# SmartSensorMainPhase.net
KiCad netlist of a schematic drawn in Altium Designer
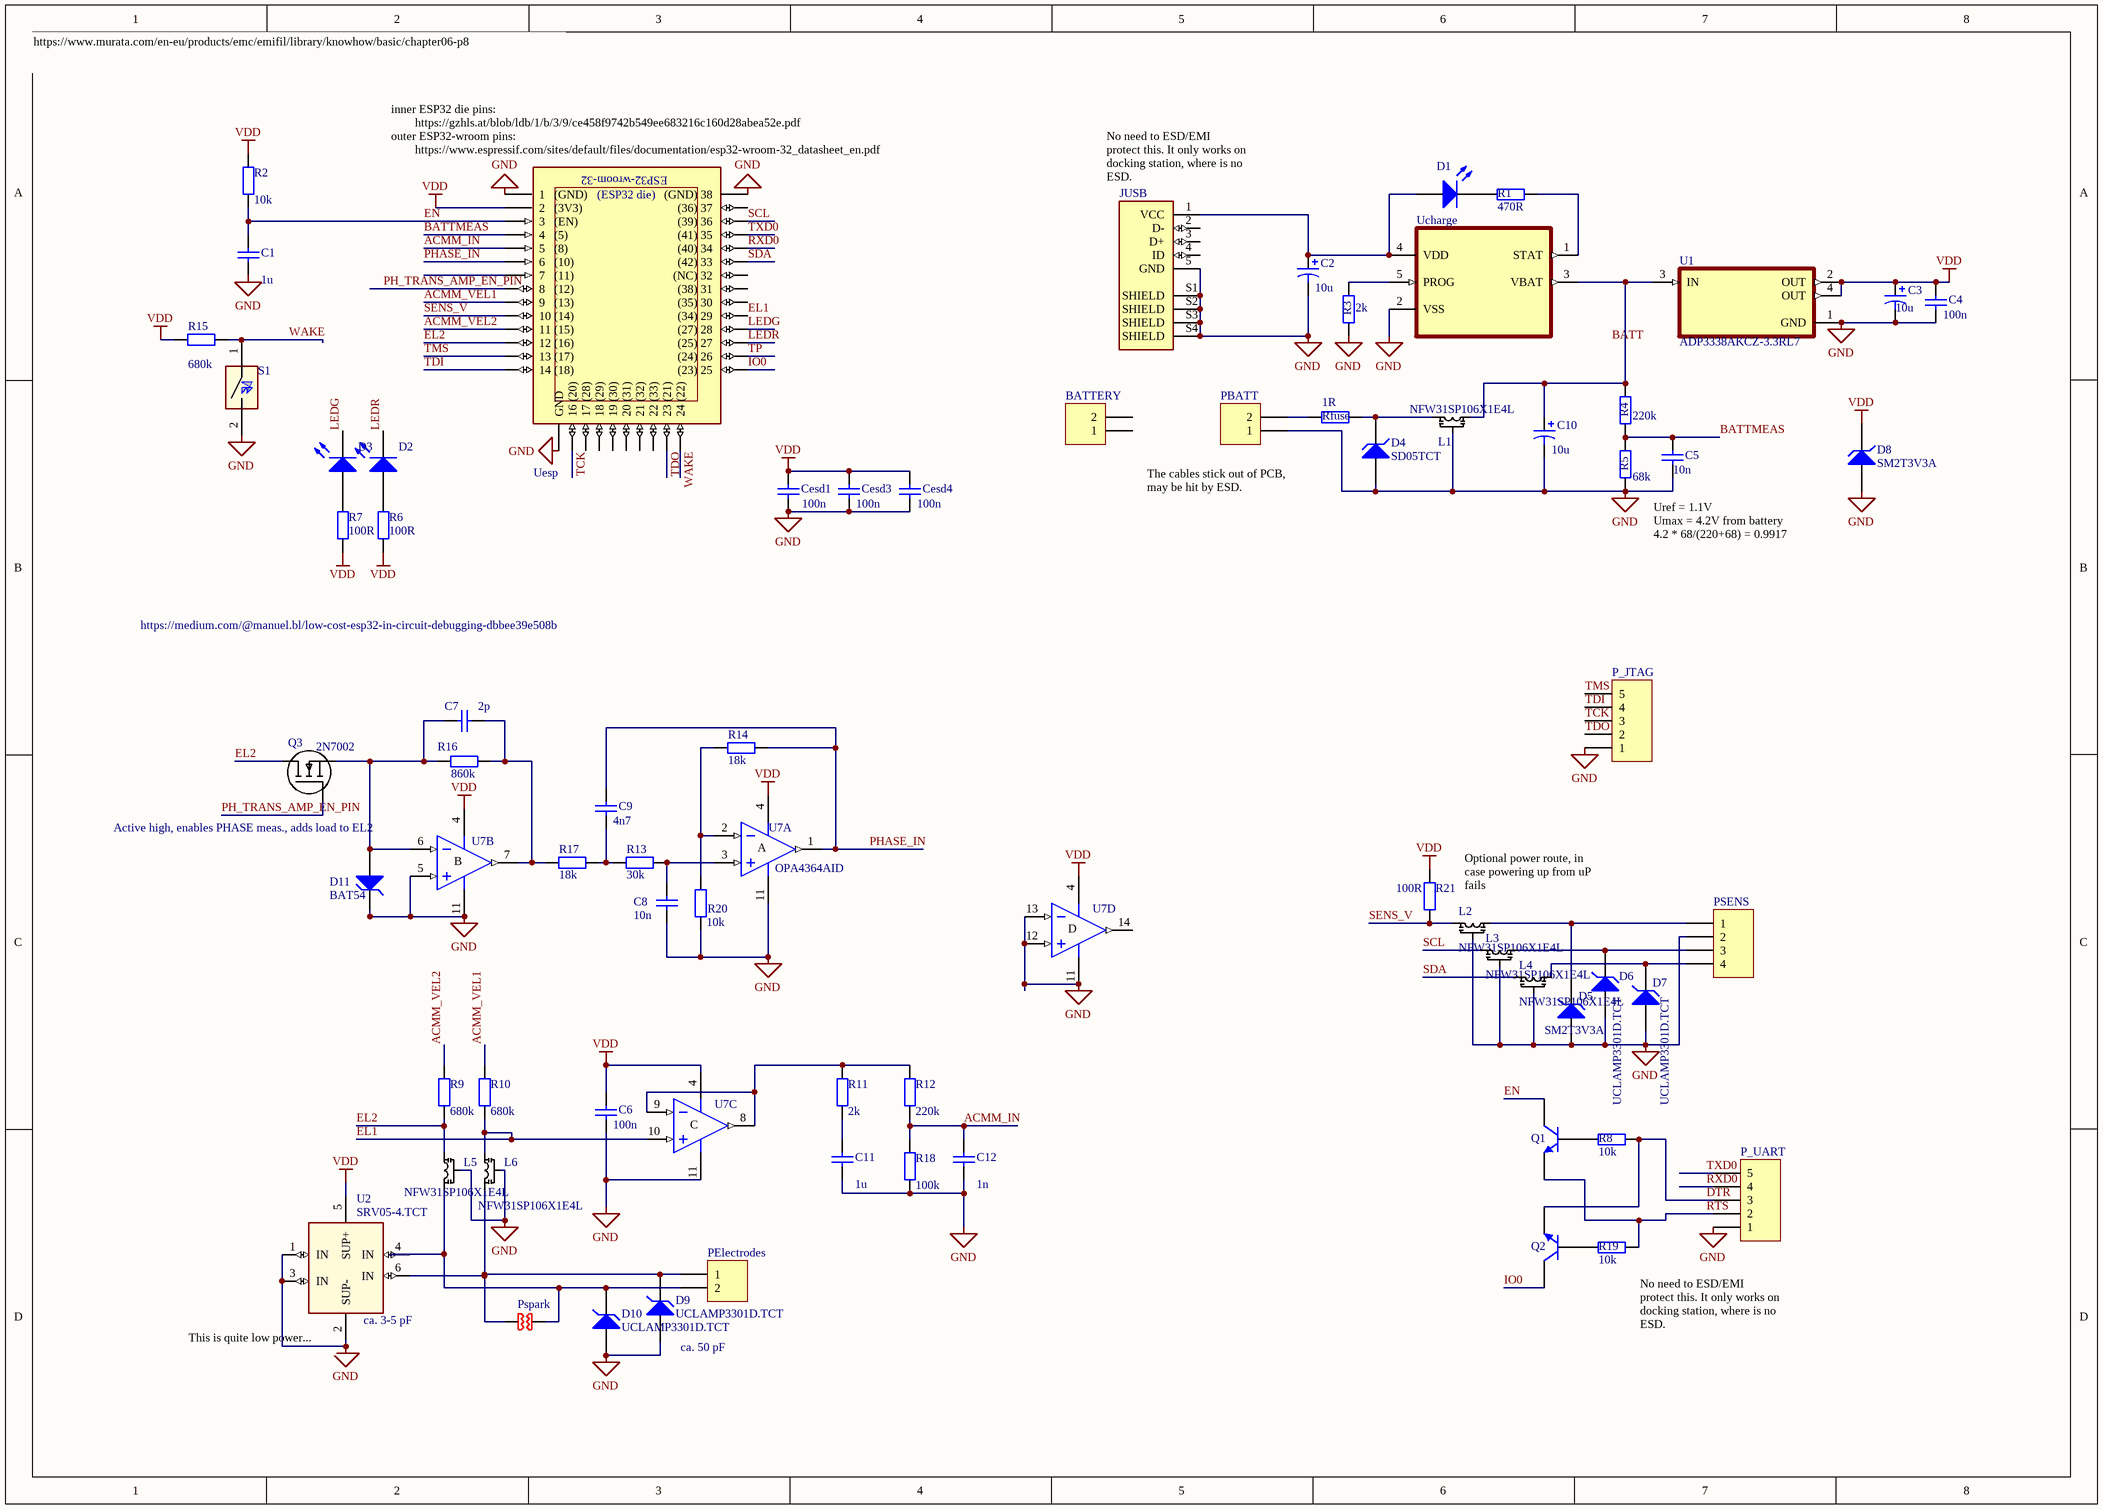
[diagram p0: SmartSensorMainPhase.SchDoc]

(export (version "E")
  (design (tool "Eeschema 10.0.6"))
  (components
    (comp (ref "BATTERY")
      (value "LI-ON 3V7 1200mAh")
      (fields
        (field (name "MP") "UF653450S")
        (field (name "MF") "SANYO")
        (field (name "PUBLISHER") "Altium Limited")
      )
      (libsource (lib "Miscellaneous Connectors") (part "Header 2"))
    )
    (comp (ref "C1")
      (value "1u")
      (footprint "C1206")
      (description "MLCC Capacitor")
      (fields
        (field (name "MF") "any")
        (field (name "MP") "MLCCxxx")
        (field (name "PUBLISHER") "Altium Limited")
      )
      (libsource (lib "Miscellaneous Devices") (part "Cap"))
    )
    (comp (ref "C2")
      (value "10u")
      (footprint "c1206")
      (description "Polarized Capacitor (Surface Mount)")
      (fields (field (name "Comment") "Cap Pol3") (field (name "PUBLISHER") "Altium Limited"))
      (libsource (lib "Miscellaneous Devices") (part "Cap Pol3"))
    )
    (comp (ref "C3")
      (value "10u")
      (footprint "C1206")
      (description "Polarized Capacitor (Surface Mount)")
      (fields (field (name "Comment") "Cap Pol3") (field (name "PUBLISHER") "Altium Limited"))
      (libsource (lib "Miscellaneous Devices") (part "Cap Pol3"))
    )
    (comp (ref "C4")
      (value "100n")
      (footprint "C1206")
      (description "MLCC Capacitor")
      (fields
        (field (name "MF") "any")
        (field (name "MP") "MLCCxxx")
        (field (name "PUBLISHER") "Altium Limited")
      )
      (libsource (lib "Miscellaneous Devices") (part "Cap"))
    )
    (comp (ref "C5")
      (value "10n")
      (footprint "C1206")
      (description "MLCC Capacitor")
      (fields
        (field (name "MF") "any")
        (field (name "MP") "MLCCxxx")
        (field (name "PUBLISHER") "Altium Limited")
      )
      (libsource (lib "Miscellaneous Devices") (part "Cap"))
    )
    (comp (ref "C6")
      (value "100n")
      (footprint "C1206")
      (description "MLCC Capacitor")
      (fields
        (field (name "MF") "any")
        (field (name "MP") "MLCCxxx")
        (field (name "PUBLISHER") "Altium Limited")
      )
      (libsource (lib "Miscellaneous Devices") (part "Cap"))
    )
    (comp (ref "C7")
      (value "2p")
      (footprint "C1206")
      (description "MLCC Capacitor")
      (fields
        (field (name "MF") "any")
        (field (name "MP") "MLCCxxx")
        (field (name "PUBLISHER") "Altium Limited")
      )
      (libsource (lib "Miscellaneous Devices") (part "Cap"))
    )
    (comp (ref "C8")
      (value "10n")
      (footprint "C1206")
      (description "MLCC Capacitor")
      (fields
        (field (name "MF") "any")
        (field (name "MP") "MLCCxxx")
        (field (name "PUBLISHER") "Altium Limited")
      )
      (libsource (lib "Miscellaneous Devices") (part "Cap"))
    )
    (comp (ref "C9")
      (value "4n7")
      (footprint "C1206")
      (description "MLCC Capacitor")
      (fields
        (field (name "MF") "any")
        (field (name "MP") "MLCCxxx")
        (field (name "PUBLISHER") "Altium Limited")
      )
      (libsource (lib "Miscellaneous Devices") (part "Cap"))
    )
    (comp (ref "C10")
      (value "10u")
      (footprint "c1206")
      (description "Polarized Capacitor (Surface Mount)")
      (fields (field (name "Comment") "Cap Pol3") (field (name "PUBLISHER") "Altium Limited"))
      (libsource (lib "Miscellaneous Devices") (part "Cap Pol3"))
    )
    (comp (ref "C11")
      (value "1u")
      (footprint "C1206")
      (description "MLCC Capacitor")
      (fields
        (field (name "MF") "any")
        (field (name "MP") "MLCCxxx")
        (field (name "PUBLISHER") "Altium Limited")
      )
      (libsource (lib "Miscellaneous Devices") (part "Cap"))
    )
    (comp (ref "C12")
      (value "1n")
      (footprint "C1206")
      (description "MLCC Capacitor")
      (fields
        (field (name "MF") "any")
        (field (name "MP") "MLCCxxx")
        (field (name "PUBLISHER") "Altium Limited")
      )
      (libsource (lib "Miscellaneous Devices") (part "Cap"))
    )
    (comp (ref "Cesd1")
      (value "100n")
      (footprint "C1206")
      (description "MLCC Capacitor")
      (fields
        (field (name "MF") "any")
        (field (name "MP") "MLCCxxx")
        (field (name "PUBLISHER") "Altium Limited")
      )
      (libsource (lib "Miscellaneous Devices") (part "Cap"))
    )
    (comp (ref "Cesd3")
      (value "100n")
      (footprint "C1206")
      (description "MLCC Capacitor")
      (fields
        (field (name "MF") "any")
        (field (name "MP") "MLCCxxx")
        (field (name "PUBLISHER") "Altium Limited")
      )
      (libsource (lib "Miscellaneous Devices") (part "Cap"))
    )
    (comp (ref "Cesd4")
      (value "100n")
      (footprint "C1206")
      (description "MLCC Capacitor")
      (fields
        (field (name "MF") "any")
        (field (name "MP") "MLCCxxx")
        (field (name "PUBLISHER") "Altium Limited")
      )
      (libsource (lib "Miscellaneous Devices") (part "Cap"))
    )
    (comp (ref "D1")
      (value "LED RED")
      (footprint "C1206")
      (fields (field (name "PUBLISHER") "Altium Limited"))
      (libsource (lib "Miscellaneous Devices") (part "LED2"))
    )
    (comp (ref "D2")
      (value "LED RED")
      (footprint "C1206")
      (fields (field (name "PUBLISHER") "Altium Limited"))
      (libsource (lib "Miscellaneous Devices") (part "LED2"))
    )
    (comp (ref "D3")
      (value "LED GREEN")
      (footprint "C1206")
      (fields (field (name "PUBLISHER") "Altium Limited"))
      (libsource (lib "Miscellaneous Devices") (part "LED2"))
    )
    (comp (ref "D4")
      (value "SD05TCT")
      (footprint "C1210")
      (description "TVS diode, no latch-up, Vstand-off > 4.5V")
      (fields (field (name "PUBLISHER") "Altium Limited"))
      (libsource (lib "Miscellaneous Devices") (part "D Zener"))
    )
    (comp (ref "D5")
      (value "SM2T3V3A")
      (footprint "C1210")
      (description "TVS Diode, Vstand-off >=3V3, no latch-up")
      (fields (field (name "PUBLISHER") "Altium Limited"))
      (libsource (lib "Miscellaneous Devices") (part "D Zener"))
    )
    (comp (ref "D6")
      (value "UCLAMP3301D.TCT")
      (footprint "C1210")
      (description "TVS diode, Vstand-off >= 3V3, low capacitance, can have latch-up")
      (fields (field (name "PUBLISHER") "Altium Limited"))
      (libsource (lib "Miscellaneous Devices") (part "D Zener"))
    )
    (comp (ref "D7")
      (value "UCLAMP3301D.TCT")
      (footprint "C1210")
      (description "TVS diode, Vstand-off >= 3V3, low capacitance, can have latch-up")
      (fields (field (name "PUBLISHER") "Altium Limited"))
      (libsource (lib "Miscellaneous Devices") (part "D Zener"))
    )
    (comp (ref "D8")
      (value "SM2T3V3A")
      (footprint "C1210")
      (description "TVS Diode, Vstand-off >=3V3, no latch-up")
      (fields (field (name "PUBLISHER") "Altium Limited"))
      (libsource (lib "Miscellaneous Devices") (part "D Zener"))
    )
    (comp (ref "D9")
      (value "UCLAMP3301D.TCT")
      (footprint "C1210")
      (description "TVS diode, Vstand-off >= 3V3, low capacitance, can have latch-up")
      (fields (field (name "PUBLISHER") "Altium Limited"))
      (libsource (lib "Miscellaneous Devices") (part "D Zener"))
    )
    (comp (ref "D10")
      (value "UCLAMP3301D.TCT")
      (footprint "C1210")
      (description "TVS diode, Vstand-off >= 3V3, low capacitance, can have latch-up")
      (fields (field (name "PUBLISHER") "Altium Limited"))
      (libsource (lib "Miscellaneous Devices") (part "D Zener"))
    )
    (comp (ref "D11")
      (value "BAT54")
      (footprint "SOT23_N")
      (description "Zener Diode, super low capacitance")
      (fields (field (name "PUBLISHER") "Altium Limited"))
      (libsource (lib "Miscellaneous Devices") (part "D Zener"))
    )
    (comp (ref "JUSB")
      (value "10118192-0001LF")
      (footprint "GCT_USB3190_REVA2")
      (description "microUSB connector")
      (fields (field (name "MF") "Amphenol"))
      (libsource (lib "USB3190_REVA2") (part "USB3190_REVA2"))
    )
    (comp (ref "L1")
      (value "NFW31SP106X1E4L")
      (footprint "1206 CLC emifil")
      (description "CLCemi")
      (fields (field (name "MF") "Murata") (field (name "PUBLISHER") "Altium Limited"))
      (libsource (lib "SmartSensorLib") (part "CLCemi"))
    )
    (comp (ref "L2")
      (value "NFW31SP106X1E4L")
      (footprint "1206 CLC emifil")
      (description "CLCemi")
      (fields (field (name "MF") "Murata") (field (name "PUBLISHER") "Altium Limited"))
      (libsource (lib "SmartSensorLib") (part "CLCemi"))
    )
    (comp (ref "L3")
      (value "NFW31SP106X1E4L")
      (footprint "1206 CLC emifil")
      (description "CLCemi")
      (fields (field (name "MF") "Murata") (field (name "PUBLISHER") "Altium Limited"))
      (libsource (lib "SmartSensorLib") (part "CLCemi"))
    )
    (comp (ref "L4")
      (value "NFW31SP106X1E4L")
      (footprint "1206 CLC emifil")
      (description "CLCemi")
      (fields (field (name "MF") "Murata") (field (name "PUBLISHER") "Altium Limited"))
      (libsource (lib "SmartSensorLib") (part "CLCemi"))
    )
    (comp (ref "L5")
      (value "NFW31SP106X1E4L")
      (footprint "1206 CLC emifil")
      (description "CLCemi")
      (fields (field (name "MF") "Murata") (field (name "PUBLISHER") "Altium Limited"))
      (libsource (lib "SmartSensorLib") (part "CLCemi"))
    )
    (comp (ref "L6")
      (value "NFW31SP106X1E4L")
      (footprint "1206 CLC emifil")
      (description "CLCemi")
      (fields (field (name "MF") "Murata") (field (name "PUBLISHER") "Altium Limited"))
      (libsource (lib "SmartSensorLib") (part "CLCemi"))
    )
    (comp (ref "PBATT")
      (value "Header 2")
      (footprint "HDR1X2")
      (description "Header, 2-Pin")
      (fields (field (name "PUBLISHER") "Altium Limited"))
      (libsource (lib "Miscellaneous Connectors") (part "Header 2"))
    )
    (comp (ref "PElectrodes")
      (value "Header 2")
      (footprint "HDR1X2")
      (description "Header, 2-Pin")
      (fields (field (name "PUBLISHER") "Altium Limited"))
      (libsource (lib "") (part "Header 2_1"))
    )
    (comp (ref "PSENS")
      (value "Header 4")
      (footprint "HDR1X4")
      (description "Header, 4-Pin")
      (fields (field (name "PUBLISHER") "Altium Limited"))
      (libsource (lib "Miscellaneous Connectors") (part "Header 4"))
    )
    (comp (ref "Pspark")
      (value "spark gap")
      (footprint "SPARKGAP10")
      (libsource (lib "PCB_Project1") (part "SparkGap"))
    )
    (comp (ref "P_JTAG")
      (value "Header 5")
      (footprint "HDR1X5")
      (description "Header, 5-Pin")
      (fields (field (name "PUBLISHER") "Altium Limited"))
      (libsource (lib "Miscellaneous Connectors") (part "Header 5"))
    )
    (comp (ref "P_UART")
      (value "Header 5")
      (footprint "HDR1X5")
      (description "Header, 5-Pin")
      (fields (field (name "PUBLISHER") "Altium Limited"))
      (libsource (lib "Miscellaneous Connectors") (part "Header 5"))
    )
    (comp (ref "Q1")
      (value "NPN")
      (footprint "SOT-23B_N")
      (description "NPN Bipolar Transistor")
      (fields
        (field (name "MP") "SS8050-L")
        (field (name "MF") "YANGJIE TECHNOLOGY")
        (field (name "PUBLISHER") "Altium Limited")
      )
      (libsource (lib "Miscellaneous Devices") (part "QNPN"))
    )
    (comp (ref "Q2")
      (value "NPN")
      (footprint "SOT-23B_N")
      (description "NPN Bipolar Transistor")
      (fields
        (field (name "MP") "SS8050-L")
        (field (name "MF") "YANGJIE TECHNOLOGY")
        (field (name "PUBLISHER") "Altium Limited")
      )
      (libsource (lib "Miscellaneous Devices") (part "QNPN"))
    )
    (comp (ref "Q3")
      (value "2N7002")
      (footprint "SOT23-GDS")
      (description "MOSFET N-CH 60V 115MA SOT-23")
      (fields (field (name "MANUFACTURER") "Fairchild Semiconductor"))
      (libsource (lib "vh_altium_library") (part "2N7002-SOT23"))
    )
    (comp (ref "R1")
      (value "470R")
      (footprint "C1206")
      (description "Resistor 5%")
      (fields (field (name "Comment") "Res2") (field (name "PUBLISHER") "Altium Limited"))
      (libsource (lib "Miscellaneous Devices") (part "Res2"))
    )
    (comp (ref "R2")
      (value "10k")
      (footprint "C1206")
      (description "Resistor 5%")
      (fields (field (name "Comment") "Res2") (field (name "PUBLISHER") "Altium Limited"))
      (libsource (lib "") (part "Res2_2"))
    )
    (comp (ref "R3")
      (value "2k")
      (footprint "C1206")
      (description "Resistor 5%")
      (fields (field (name "Comment") "Res2") (field (name "PUBLISHER") "Altium Limited"))
      (libsource (lib "") (part "Res2_2"))
    )
    (comp (ref "R4")
      (value "220k")
      (footprint "C1206")
      (description "Resistor 1%")
      (fields (field (name "Comment") "Res2") (field (name "PUBLISHER") "Altium Limited"))
      (libsource (lib "") (part "Res2_3"))
    )
    (comp (ref "R5")
      (value "68k")
      (footprint "C1206")
      (description "Resistor 1%")
      (fields (field (name "Comment") "Res2") (field (name "PUBLISHER") "Altium Limited"))
      (libsource (lib "") (part "Res2_3"))
    )
    (comp (ref "R6")
      (value "100R")
      (footprint "C1206")
      (description "Resistor 5%")
      (fields (field (name "Comment") "Res2") (field (name "PUBLISHER") "Altium Limited"))
      (libsource (lib "") (part "Res2_2"))
    )
    (comp (ref "R7")
      (value "100R")
      (footprint "C1206")
      (description "Resistor 5%")
      (fields (field (name "Comment") "Res2") (field (name "PUBLISHER") "Altium Limited"))
      (libsource (lib "") (part "Res2_2"))
    )
    (comp (ref "R8")
      (value "10k")
      (footprint "C1206")
      (description "Resistor 5%")
      (fields (field (name "Comment") "Res2") (field (name "PUBLISHER") "Altium Limited"))
      (libsource (lib "") (part "Res2_2"))
    )
    (comp (ref "R9")
      (value "680k")
      (footprint "C1206")
      (description "Resistor 5%")
      (fields (field (name "Comment") "Res2") (field (name "PUBLISHER") "Altium Limited"))
      (libsource (lib "") (part "Res2_2"))
    )
    (comp (ref "R10")
      (value "680k")
      (footprint "C1206")
      (description "Resistor 5%")
      (fields (field (name "Comment") "Res2") (field (name "PUBLISHER") "Altium Limited"))
      (libsource (lib "") (part "Res2_2"))
    )
    (comp (ref "R11")
      (value "2k")
      (footprint "C1206")
      (description "Resistor 5%")
      (fields (field (name "Comment") "Res2") (field (name "PUBLISHER") "Altium Limited"))
      (libsource (lib "") (part "Res2_2"))
    )
    (comp (ref "R12")
      (value "220k")
      (footprint "C1206")
      (description "Resistor 5%")
      (fields (field (name "Comment") "Res2") (field (name "PUBLISHER") "Altium Limited"))
      (libsource (lib "") (part "Res2_2"))
    )
    (comp (ref "R13")
      (value "30k")
      (footprint "C1206")
      (description "Resistor 1%")
      (fields (field (name "Comment") "Res2") (field (name "PUBLISHER") "Altium Limited"))
      (libsource (lib "Miscellaneous Devices") (part "Res2"))
    )
    (comp (ref "R14")
      (value "18k")
      (footprint "C1206")
      (description "Resistor 1%")
      (fields (field (name "Comment") "Res2") (field (name "PUBLISHER") "Altium Limited"))
      (libsource (lib "Miscellaneous Devices") (part "Res2"))
    )
    (comp (ref "R15")
      (value "680k")
      (footprint "C1206")
      (description "Resistor 5%")
      (fields (field (name "Comment") "Res2") (field (name "PUBLISHER") "Altium Limited"))
      (libsource (lib "Miscellaneous Devices") (part "Res2"))
    )
    (comp (ref "R16")
      (value "860k")
      (footprint "C1206")
      (description "Resistor 1%")
      (fields (field (name "Comment") "Res2") (field (name "PUBLISHER") "Altium Limited"))
      (libsource (lib "Miscellaneous Devices") (part "Res2"))
    )
    (comp (ref "R17")
      (value "18k")
      (footprint "C1206")
      (description "Resistor 1%")
      (fields (field (name "Comment") "Res2") (field (name "PUBLISHER") "Altium Limited"))
      (libsource (lib "Miscellaneous Devices") (part "Res2"))
    )
    (comp (ref "R18")
      (value "100k")
      (footprint "C1206")
      (description "Resistor 5%")
      (fields (field (name "Comment") "Res2") (field (name "PUBLISHER") "Altium Limited"))
      (libsource (lib "") (part "Res2_2"))
    )
    (comp (ref "R19")
      (value "10k")
      (footprint "C1206")
      (description "Resistor 5%")
      (fields (field (name "Comment") "Res2") (field (name "PUBLISHER") "Altium Limited"))
      (libsource (lib "") (part "Res2_2"))
    )
    (comp (ref "R20")
      (value "10k")
      (footprint "C1206")
      (description "Resistor 1%")
      (fields (field (name "Comment") "Res2") (field (name "PUBLISHER") "Altium Limited"))
      (libsource (lib "") (part "Res2_1"))
    )
    (comp (ref "R21")
      (value "100R")
      (footprint "c1206")
      (description "Resistor 5%")
      (fields (field (name "Comment") "Res2") (field (name "PUBLISHER") "Altium Limited"))
      (libsource (lib "") (part "Res2_2"))
    )
    (comp (ref "Rfuse")
      (value "1R")
      (footprint "C1206")
      (description "Resistor 5%")
      (fields (field (name "Comment") "Res2") (field (name "PUBLISHER") "Altium Limited"))
      (libsource (lib "") (part "Res2_1"))
    )
    (comp (ref "S1")
      (value "VBS030600")
      (footprint "VBS030600")
      (description "Movement sensor")
      (fields (field (name "MF") "ONCQUE"))
      (libsource (lib "SRV05-4.TCT") (part "VBS030600"))
    )
    (comp (ref "U1")
      (value "ADP3338AKCZ-3.3RL7")
      (footprint "SOT230P700X180-4N")
      (description "LDO voltage regulator")
      (fields (field (name "MF") "Analog Devices"))
      (libsource (lib "ADP3338AKCZ-5-R7") (part "ADP3338AKCZ-5-R7"))
    )
    (comp (ref "U2")
      (value "SRV05-4.TCT")
      (footprint "SRV05-4.TCT:SOT95P280X145-6N")
      (description "17.5V Clamp 12A _8/20µs_ Ipp Tvs Diode Surface Mount SOT-23-6")
      (fields (field (name "MF") "Semtech"))
      (libsource (lib "SnapEDAsch") (part "SRV05-4.TCT"))
    )
    (comp (ref "U7")
      (value "OPA4364AID")
      (footprint "SO-14_N")
      (description "Quad Picoampere Input Current Bipolar Operational Amplifier")
      (fields (field (name "MF") "TI") (field (name "PUBLISHER") "Altium Limited"))
      (libsource (lib "AD Operational Amplifier") (part "AD704AN"))
    )
    (comp (ref "Ucharge")
      (value "MCP73831T-2ACI/OT")
      (footprint "SOT23-5")
      (description "Charger IC Lithium Ion/Polymer SOT-23-5")
      (fields (field (name "MF") "Microchip"))
      (libsource (lib "MCP73831T-2ACI_OT") (part "MCP73831T-2ACI/OT"))
    )
    (comp (ref "Uesp")
      (value "ESP32-WROOM-32")
      (footprint "ESP32-WROOM-32:MODULE_ESP32-WROOM-32")
      (description "Bluetooth, WiFi Transceiver Module 2.4GHz ~ 2.5GHz Surface Mount")
      (fields (field (name "MF") "Espressif Systems") (field (name "DIGI-KEY_PART_NUMBER") "1904-1010-1-ND"))
      (libsource (lib "PCB_Project1") (part "ESP32-WROOM-32"))
    )
  )
  (nets
    (net (code "1") (name "/ACMM_IN") (class "Default")
      (node (ref "C12") (pin "2") (pinfunction "2_2") (pintype "passive"))
      (node (ref "R12") (pin "1") (pinfunction "1_1") (pintype "passive"))
      (node (ref "R18") (pin "2") (pinfunction "2_2") (pintype "passive"))
      (node (ref "Uesp") (pin "5") (pinfunction "5___(8)_5") (pintype "input"))
    )
    (net (code "2") (name "/ACMM_VEL1") (class "Default")
      (node (ref "R10") (pin "2") (pinfunction "2_2") (pintype "passive"))
      (node (ref "Uesp") (pin "9") (pinfunction "9___(13)_9") (pintype "bidirectional"))
    )
    (net (code "3") (name "/ACMM_VEL2") (class "Default")
      (node (ref "R9") (pin "2") (pinfunction "2_2") (pintype "passive"))
      (node (ref "Uesp") (pin "11") (pinfunction "11_(15)_11") (pintype "bidirectional"))
    )
    (net (code "5") (name "/BATTMEAS") (class "Default")
      (node (ref "C5") (pin "2") (pinfunction "2_2") (pintype "passive"))
      (node (ref "R4") (pin "1") (pinfunction "1_1") (pintype "passive"))
      (node (ref "R5") (pin "2") (pinfunction "2_2") (pintype "passive"))
      (node (ref "Uesp") (pin "4") (pinfunction "4___(5)_4") (pintype "input"))
    )
    (net (code "6") (name "/DTR") (class "Default")
      (node (ref "P_UART") (pin "3") (pinfunction "3_3") (pintype "passive"))
      (node (ref "Q2") (pin "2") (pinfunction "E_2") (pintype "passive"))
      (node (ref "R8") (pin "2") (pinfunction "2_2") (pintype "passive"))
    )
    (net (code "7") (name "/EL1") (class "Default")
      (node (ref "L6") (pin "3") (pinfunction "3_3") (pintype "passive"))
      (node (ref "R10") (pin "1") (pinfunction "1_1") (pintype "passive"))
      (node (ref "U7") (pin "10") (pinfunction "IN+_10") (pintype "input"))
      (node (ref "Uesp") (pin "29") (pinfunction "(34)_29_29") (pintype "bidirectional"))
    )
    (net (code "8") (name "/EL2") (class "Default")
      (node (ref "L5") (pin "3") (pinfunction "3_3") (pintype "passive"))
      (node (ref "Q3") (pin "D") (pintype "passive"))
      (node (ref "R9") (pin "1") (pinfunction "1_1") (pintype "passive"))
      (node (ref "Uesp") (pin "12") (pinfunction "12_(16)_12") (pintype "bidirectional"))
    )
    (net (code "9") (name "/EN") (class "Default")
      (node (ref "C1") (pin "2") (pinfunction "2_2") (pintype "passive"))
      (node (ref "Q1") (pin "3") (pinfunction "C_3") (pintype "passive"))
      (node (ref "R2") (pin "1") (pinfunction "1_1") (pintype "passive"))
      (node (ref "Uesp") (pin "3") (pinfunction "3___(EN)_3") (pintype "input"))
    )
    (net (code "10") (name "/IO0") (class "Default")
      (node (ref "Q2") (pin "3") (pinfunction "C_3") (pintype "passive"))
      (node (ref "Uesp") (pin "25") (pinfunction "(23)_25_25") (pintype "bidirectional"))
    )
    (net (code "11") (name "/LEDG") (class "Default")
      (node (ref "D3") (pin "2") (pinfunction "K_2") (pintype "passive"))
      (node (ref "Uesp") (pin "28") (pinfunction "(27)_28_28") (pintype "bidirectional"))
    )
    (net (code "12") (name "/LEDR") (class "Default")
      (node (ref "D2") (pin "2") (pinfunction "K_2") (pintype "passive"))
      (node (ref "Uesp") (pin "27") (pinfunction "(25)_27_27") (pintype "bidirectional"))
    )
    (net (code "13") (name "/PHASE_IN") (class "Default")
      (node (ref "C9") (pin "2") (pinfunction "2_2") (pintype "passive"))
      (node (ref "R14") (pin "1") (pinfunction "1_1") (pintype "passive"))
      (node (ref "U7") (pin "1") (pinfunction "OUT_1") (pintype "output"))
      (node (ref "Uesp") (pin "6") (pinfunction "6___(10)_6") (pintype "input"))
    )
    (net (code "14") (name "/PH_TRANS_AMP_EN_PIN") (class "Default")
      (node (ref "Q3") (pin "G") (pintype "passive"))
      (node (ref "Uesp") (pin "8") (pinfunction "8___(12)_8") (pintype "bidirectional"))
    )
    (net (code "15") (name "/RTS") (class "Default")
      (node (ref "P_UART") (pin "2") (pinfunction "2_2") (pintype "passive"))
      (node (ref "Q1") (pin "2") (pinfunction "E_2") (pintype "passive"))
      (node (ref "R19") (pin "2") (pinfunction "2_2") (pintype "passive"))
    )
    (net (code "16") (name "/RXD0") (class "Default")
      (node (ref "P_UART") (pin "4") (pinfunction "4_4") (pintype "passive"))
      (node (ref "Uesp") (pin "34") (pinfunction "(40)_34_34") (pintype "bidirectional"))
    )
    (net (code "17") (name "/SCL") (class "Default")
      (node (ref "L3") (pin "1") (pinfunction "1_1") (pintype "passive"))
      (node (ref "Uesp") (pin "36") (pinfunction "(39)_36_36") (pintype "bidirectional"))
    )
    (net (code "18") (name "/SDA") (class "Default")
      (node (ref "L4") (pin "1") (pinfunction "1_1") (pintype "passive"))
      (node (ref "Uesp") (pin "33") (pinfunction "(42)_33_33") (pintype "bidirectional"))
    )
    (net (code "19") (name "/SENS_V") (class "Default")
      (node (ref "L2") (pin "1") (pinfunction "1_1") (pintype "passive"))
      (node (ref "R21") (pin "1") (pinfunction "1_1") (pintype "passive"))
      (node (ref "Uesp") (pin "10") (pinfunction "10_(14)_10") (pintype "bidirectional"))
    )
    (net (code "20") (name "/TCK") (class "Default")
      (node (ref "P_JTAG") (pin "3") (pinfunction "3_3") (pintype "passive"))
      (node (ref "Uesp") (pin "16") (pinfunction "16_(20)_16") (pintype "bidirectional"))
    )
    (net (code "21") (name "/TDI") (class "Default")
      (node (ref "P_JTAG") (pin "4") (pinfunction "4_4") (pintype "passive"))
      (node (ref "Uesp") (pin "14") (pinfunction "14_(18)_14") (pintype "bidirectional"))
    )
    (net (code "22") (name "/TDO") (class "Default")
      (node (ref "P_JTAG") (pin "2") (pinfunction "2_2") (pintype "passive"))
      (node (ref "Uesp") (pin "23") (pinfunction "23_(21)_23") (pintype "bidirectional"))
    )
    (net (code "23") (name "/TMS") (class "Default")
      (node (ref "P_JTAG") (pin "5") (pinfunction "5_5") (pintype "passive"))
      (node (ref "Uesp") (pin "13") (pinfunction "13_(17)_13") (pintype "bidirectional"))
    )
    (net (code "24") (name "/TP") (class "Default")
      (node (ref "Uesp") (pin "26") (pinfunction "(24)_26_26") (pintype "bidirectional"))
    )
    (net (code "25") (name "/TXD0") (class "Default")
      (node (ref "P_UART") (pin "5") (pinfunction "5_5") (pintype "passive"))
      (node (ref "Uesp") (pin "35") (pinfunction "(41)_35_35") (pintype "bidirectional"))
    )
    (net (code "26") (name "/WAKE") (class "Default")
      (node (ref "R15") (pin "1") (pinfunction "1_1") (pintype "passive"))
      (node (ref "S1") (pin "1") (pinfunction "IN_1") (pintype "open_collector"))
      (node (ref "Uesp") (pin "24") (pinfunction "24_(22)_24") (pintype "bidirectional"))
    )
    (net (code "27") (name "GND") (class "Default")
      (node (ref "C1") (pin "1") (pinfunction "1_1") (pintype "passive"))
      (node (ref "C10") (pin "2") (pinfunction "2_2") (pintype "passive"))
      (node (ref "C11") (pin "1") (pinfunction "1_1") (pintype "passive"))
      (node (ref "C12") (pin "1") (pinfunction "1_1") (pintype "passive"))
      (node (ref "C2") (pin "2") (pinfunction "2_2") (pintype "passive"))
      (node (ref "C3") (pin "2") (pinfunction "2_2") (pintype "passive"))
      (node (ref "C4") (pin "1") (pinfunction "1_1") (pintype "passive"))
      (node (ref "C5") (pin "1") (pinfunction "1_1") (pintype "passive"))
      (node (ref "C6") (pin "1") (pinfunction "1_1") (pintype "passive"))
      (node (ref "C8") (pin "1") (pinfunction "1_1") (pintype "passive"))
      (node (ref "Cesd1") (pin "1") (pinfunction "1_1") (pintype "passive"))
      (node (ref "Cesd3") (pin "1") (pinfunction "1_1") (pintype "passive"))
      (node (ref "Cesd4") (pin "1") (pinfunction "1_1") (pintype "passive"))
      (node (ref "D10") (pin "1") (pinfunction "A_1") (pintype "passive"))
      (node (ref "D11") (pin "2") (pinfunction "K_2") (pintype "passive"))
      (node (ref "D4") (pin "1") (pinfunction "A_1") (pintype "passive"))
      (node (ref "D5") (pin "1") (pinfunction "A_1") (pintype "passive"))
      (node (ref "D6") (pin "1") (pinfunction "A_1") (pintype "passive"))
      (node (ref "D7") (pin "1") (pinfunction "A_1") (pintype "passive"))
      (node (ref "D8") (pin "1") (pinfunction "A_1") (pintype "passive"))
      (node (ref "D9") (pin "1") (pinfunction "A_1") (pintype "passive"))
      (node (ref "JUSB") (pin "5") (pinfunction "GND_5") (pintype "power_in"))
      (node (ref "JUSB") (pin "S1") (pinfunction "SHIELD_S1") (pintype "passive"))
      (node (ref "JUSB") (pin "S2") (pinfunction "SHIELD_S2") (pintype "passive"))
      (node (ref "JUSB") (pin "S3") (pinfunction "SHIELD_S3") (pintype "passive"))
      (node (ref "JUSB") (pin "S4") (pinfunction "SHIELD_S4") (pintype "passive"))
      (node (ref "L1") (pin "2") (pinfunction "2_2") (pintype "power_in"))
      (node (ref "L2") (pin "2") (pinfunction "2_2") (pintype "power_in"))
      (node (ref "L3") (pin "2") (pinfunction "2_2") (pintype "power_in"))
      (node (ref "L4") (pin "2") (pinfunction "2_2") (pintype "power_in"))
      (node (ref "L5") (pin "2") (pinfunction "2_2") (pintype "power_in"))
      (node (ref "L6") (pin "2") (pinfunction "2_2") (pintype "power_in"))
      (node (ref "PBATT") (pin "1") (pinfunction "1_1") (pintype "passive"))
      (node (ref "PSENS") (pin "2") (pinfunction "2_2") (pintype "passive"))
      (node (ref "P_JTAG") (pin "1") (pinfunction "1_1") (pintype "passive"))
      (node (ref "P_UART") (pin "1") (pinfunction "1_1") (pintype "passive"))
      (node (ref "R18") (pin "1") (pinfunction "1_1") (pintype "passive"))
      (node (ref "R20") (pin "2") (pinfunction "2_2") (pintype "passive"))
      (node (ref "R3") (pin "1") (pinfunction "1_1") (pintype "passive"))
      (node (ref "R5") (pin "1") (pinfunction "1_1") (pintype "passive"))
      (node (ref "S1") (pin "2") (pinfunction "IN_2") (pintype "open_collector"))
      (node (ref "U1") (pin "1") (pinfunction "GND_1") (pintype "power_in"))
      (node (ref "U2") (pin "1") (pinfunction "IN_1") (pintype "bidirectional"))
      (node (ref "U2") (pin "2") (pinfunction "SUP-_2") (pintype "power_in"))
      (node (ref "U2") (pin "3") (pinfunction "IN_3") (pintype "bidirectional"))
      (node (ref "U7") (pin "11") (pinfunction "V-_11") (pintype "power_in"))
      (node (ref "U7") (pin "12") (pinfunction "IN+_12") (pintype "input"))
      (node (ref "U7") (pin "13") (pinfunction "IN-_13") (pintype "input"))
      (node (ref "U7") (pin "5") (pinfunction "IN+_5") (pintype "input"))
      (node (ref "Ucharge") (pin "2") (pinfunction "VSS_2") (pintype "power_in"))
      (node (ref "Uesp") (pin "1") (pinfunction "1___(GND)_1") (pintype "power_in"))
      (node (ref "Uesp") (pin "15") (pinfunction "GND_15") (pintype "power_in"))
      (node (ref "Uesp") (pin "38") (pinfunction "(GND)_38_38") (pintype "power_in"))
    )
    (net (code "28") (name "Net-(C9-Pad1)") (class "Default")
      (node (ref "C9") (pin "1") (pinfunction "1_1") (pintype "passive"))
      (node (ref "R13") (pin "2") (pinfunction "2_2") (pintype "passive"))
      (node (ref "R17") (pin "1") (pinfunction "1_1") (pintype "passive"))
    )
    (net (code "29") (name "Net-(C11-Pad2)") (class "Default")
      (node (ref "C11") (pin "2") (pinfunction "2_2") (pintype "passive"))
      (node (ref "R11") (pin "1") (pinfunction "1_1") (pintype "passive"))
    )
    (net (code "30") (name "Net-(D1-A)") (class "Default")
      (node (ref "C2") (pin "1") (pinfunction "1_1") (pintype "passive"))
      (node (ref "D1") (pin "1") (pinfunction "A_1") (pintype "passive"))
      (node (ref "JUSB") (pin "1") (pinfunction "VCC_1") (pintype "power_in"))
      (node (ref "Ucharge") (pin "4") (pinfunction "VDD_4") (pintype "power_in"))
    )
    (net (code "31") (name "Net-(D1-K)") (class "Default")
      (node (ref "D1") (pin "2") (pinfunction "K_2") (pintype "passive"))
      (node (ref "R1") (pin "2") (pinfunction "2_2") (pintype "passive"))
    )
    (net (code "32") (name "Net-(D2-A)") (class "Default")
      (node (ref "D2") (pin "1") (pinfunction "A_1") (pintype "passive"))
      (node (ref "R6") (pin "2") (pinfunction "2_2") (pintype "passive"))
    )
    (net (code "33") (name "Net-(D3-A)") (class "Default")
      (node (ref "D3") (pin "1") (pinfunction "A_1") (pintype "passive"))
      (node (ref "R7") (pin "2") (pinfunction "2_2") (pintype "passive"))
    )
    (net (code "34") (name "Net-(D4-K)") (class "Default")
      (node (ref "D4") (pin "2") (pinfunction "K_2") (pintype "passive"))
      (node (ref "L1") (pin "1") (pinfunction "1_1") (pintype "passive"))
      (node (ref "Rfuse") (pin "1") (pinfunction "1_1") (pintype "passive"))
    )
    (net (code "35") (name "Net-(D5-K)") (class "Default")
      (node (ref "D5") (pin "2") (pinfunction "K_2") (pintype "passive"))
      (node (ref "L2") (pin "3") (pinfunction "3_3") (pintype "passive"))
      (node (ref "PSENS") (pin "1") (pinfunction "1_1") (pintype "passive"))
    )
    (net (code "36") (name "Net-(D6-K)") (class "Default")
      (node (ref "D6") (pin "2") (pinfunction "K_2") (pintype "passive"))
      (node (ref "L3") (pin "3") (pinfunction "3_3") (pintype "passive"))
      (node (ref "PSENS") (pin "3") (pinfunction "3_3") (pintype "passive"))
    )
    (net (code "37") (name "Net-(D7-K)") (class "Default")
      (node (ref "D7") (pin "2") (pinfunction "K_2") (pintype "passive"))
      (node (ref "L4") (pin "3") (pinfunction "3_3") (pintype "passive"))
      (node (ref "PSENS") (pin "4") (pinfunction "4_4") (pintype "passive"))
    )
    (net (code "38") (name "Net-(D9-K)") (class "Default")
      (node (ref "D9") (pin "2") (pinfunction "K_2") (pintype "passive"))
      (node (ref "L6") (pin "1") (pinfunction "1_1") (pintype "passive"))
      (node (ref "PElectrodes") (pin "1") (pinfunction "1_1") (pintype "passive"))
      (node (ref "Pspark") (pin "1") (pinfunction "1_1") (pintype "passive"))
      (node (ref "U2") (pin "6") (pinfunction "IN_6") (pintype "bidirectional"))
    )
    (net (code "39") (name "Net-(D10-K)") (class "Default")
      (node (ref "D10") (pin "2") (pinfunction "K_2") (pintype "passive"))
      (node (ref "L5") (pin "1") (pinfunction "1_1") (pintype "passive"))
      (node (ref "PElectrodes") (pin "2") (pinfunction "2_2") (pintype "passive"))
      (node (ref "Pspark") (pin "2") (pinfunction "2_2") (pintype "passive"))
      (node (ref "U2") (pin "4") (pinfunction "IN_4") (pintype "bidirectional"))
    )
    (net (code "40") (name "Net-(D11-A)") (class "Default")
      (node (ref "C7") (pin "2") (pinfunction "2_2") (pintype "passive"))
      (node (ref "D11") (pin "1") (pinfunction "A_1") (pintype "passive"))
      (node (ref "Q3") (pin "S") (pintype "passive"))
      (node (ref "R16") (pin "2") (pinfunction "2_2") (pintype "passive"))
      (node (ref "U7") (pin "6") (pinfunction "IN-_6") (pintype "input"))
    )
    (net (code "41") (name "Net-(PBATT-Pad2)") (class "Default")
      (node (ref "PBATT") (pin "2") (pinfunction "2_2") (pintype "passive"))
      (node (ref "Rfuse") (pin "2") (pinfunction "2_2") (pintype "passive"))
    )
    (net (code "42") (name "Net-(Q1-B)") (class "Default")
      (node (ref "Q1") (pin "1") (pinfunction "B_1") (pintype "passive"))
      (node (ref "R8") (pin "1") (pinfunction "1_1") (pintype "passive"))
    )
    (net (code "43") (name "Net-(Q2-B)") (class "Default")
      (node (ref "Q2") (pin "1") (pinfunction "B_1") (pintype "passive"))
      (node (ref "R19") (pin "1") (pinfunction "1_1") (pintype "passive"))
    )
    (net (code "44") (name "Net-(U1-IN)") (class "Default")
      (node (ref "C10") (pin "1") (pinfunction "1_1") (pintype "passive"))
      (node (ref "L1") (pin "3") (pinfunction "3_3") (pintype "passive"))
      (node (ref "R4") (pin "2") (pinfunction "2_2") (pintype "passive"))
      (node (ref "U1") (pin "3") (pinfunction "IN_3") (pintype "input"))
      (node (ref "Ucharge") (pin "3") (pinfunction "VBAT_3") (pintype "output"))
    )
    (net (code "45") (name "Net-(U7A-IN+)") (class "Default")
      (node (ref "C8") (pin "2") (pinfunction "2_2") (pintype "passive"))
      (node (ref "R13") (pin "1") (pinfunction "1_1") (pintype "passive"))
      (node (ref "U7") (pin "3") (pinfunction "IN+_3") (pintype "input"))
    )
    (net (code "46") (name "Net-(U7A-IN-)") (class "Default")
      (node (ref "R14") (pin "2") (pinfunction "2_2") (pintype "passive"))
      (node (ref "R20") (pin "1") (pinfunction "1_1") (pintype "passive"))
      (node (ref "U7") (pin "2") (pinfunction "IN-_2") (pintype "input"))
    )
    (net (code "47") (name "Net-(U7B-OUT)") (class "Default")
      (node (ref "C7") (pin "1") (pinfunction "1_1") (pintype "passive"))
      (node (ref "R16") (pin "1") (pinfunction "1_1") (pintype "passive"))
      (node (ref "R17") (pin "2") (pinfunction "2_2") (pintype "passive"))
      (node (ref "U7") (pin "7") (pinfunction "OUT_7") (pintype "output"))
    )
    (net (code "48") (name "Net-(U7C-IN-)") (class "Default")
      (node (ref "R11") (pin "2") (pinfunction "2_2") (pintype "passive"))
      (node (ref "R12") (pin "2") (pinfunction "2_2") (pintype "passive"))
      (node (ref "U7") (pin "8") (pinfunction "OUT_8") (pintype "output"))
      (node (ref "U7") (pin "9") (pinfunction "IN-_9") (pintype "input"))
    )
    (net (code "49") (name "Net-(Ucharge-PROG)") (class "Default")
      (node (ref "R3") (pin "2") (pinfunction "2_2") (pintype "passive"))
      (node (ref "Ucharge") (pin "5") (pinfunction "PROG_5") (pintype "input"))
    )
    (net (code "50") (name "Net-(Ucharge-STAT)") (class "Default")
      (node (ref "R1") (pin "1") (pinfunction "1_1") (pintype "passive"))
      (node (ref "Ucharge") (pin "1") (pinfunction "STAT_1") (pintype "output"))
    )
    (net (code "51") (name "VDD") (class "Default")
      (node (ref "C3") (pin "1") (pinfunction "1_1") (pintype "passive"))
      (node (ref "C4") (pin "2") (pinfunction "2_2") (pintype "passive"))
      (node (ref "C6") (pin "2") (pinfunction "2_2") (pintype "passive"))
      (node (ref "Cesd1") (pin "2") (pinfunction "2_2") (pintype "passive"))
      (node (ref "Cesd3") (pin "2") (pinfunction "2_2") (pintype "passive"))
      (node (ref "Cesd4") (pin "2") (pinfunction "2_2") (pintype "passive"))
      (node (ref "D8") (pin "2") (pinfunction "K_2") (pintype "passive"))
      (node (ref "R15") (pin "2") (pinfunction "2_2") (pintype "passive"))
      (node (ref "R2") (pin "2") (pinfunction "2_2") (pintype "passive"))
      (node (ref "R21") (pin "2") (pinfunction "2_2") (pintype "passive"))
      (node (ref "R6") (pin "1") (pinfunction "1_1") (pintype "passive"))
      (node (ref "R7") (pin "1") (pinfunction "1_1") (pintype "passive"))
      (node (ref "U1") (pin "2") (pinfunction "OUT_2") (pintype "output"))
      (node (ref "U1") (pin "4") (pinfunction "OUT_4") (pintype "output"))
      (node (ref "U2") (pin "5") (pinfunction "SUP+_5") (pintype "power_in"))
      (node (ref "U7") (pin "4") (pinfunction "V+_4") (pintype "power_in"))
      (node (ref "Uesp") (pin "2") (pinfunction "2___(3V3)_2") (pintype "power_in"))
    )
    (net (code "52") (name "unconnected-(BATTERY-Pad1)") (class "Default")
      (node (ref "BATTERY") (pin "1") (pinfunction "1_1") (pintype "passive"))
    )
    (net (code "53") (name "unconnected-(BATTERY-Pad2)") (class "Default")
      (node (ref "BATTERY") (pin "2") (pinfunction "2_2") (pintype "passive"))
    )
    (net (code "54") (name "unconnected-(JUSB-D+-Pad3)") (class "Default")
      (node (ref "JUSB") (pin "3") (pinfunction "D+_3") (pintype "bidirectional"))
    )
    (net (code "55") (name "unconnected-(JUSB-D--Pad2)") (class "Default")
      (node (ref "JUSB") (pin "2") (pinfunction "D-_2") (pintype "bidirectional"))
    )
    (net (code "56") (name "unconnected-(JUSB-ID-Pad4)") (class "Default")
      (node (ref "JUSB") (pin "4") (pinfunction "ID_4") (pintype "bidirectional"))
    )
    (net (code "57") (name "unconnected-(U7D-OUT-Pad14)") (class "Default")
      (node (ref "U7") (pin "14") (pinfunction "OUT_14") (pintype "output"))
    )
    (net (code "58") (name "unconnected-(Uesp-(35)_30-Pad30)") (class "Default")
      (node (ref "Uesp") (pin "30") (pinfunction "(35)_30_30") (pintype "bidirectional"))
    )
    (net (code "59") (name "unconnected-(Uesp-(36)_37-Pad37)") (class "Default")
      (node (ref "Uesp") (pin "37") (pinfunction "(36)_37_37") (pintype "bidirectional"))
    )
    (net (code "60") (name "unconnected-(Uesp-(38)_31-Pad31)") (class "Default")
      (node (ref "Uesp") (pin "31") (pinfunction "(38)_31_31") (pintype "bidirectional"))
    )
    (net (code "61") (name "unconnected-(Uesp-(NC)_32-Pad32)") (class "Default")
      (node (ref "Uesp") (pin "32") (pinfunction "(NC)_32_32") (pintype "bidirectional"))
    )
    (net (code "62") (name "unconnected-(Uesp-7___(11)-Pad7)") (class "Default")
      (node (ref "Uesp") (pin "7") (pinfunction "7___(11)_7") (pintype "input"))
    )
    (net (code "63") (name "unconnected-(Uesp-17_(28)-Pad17)") (class "Default")
      (node (ref "Uesp") (pin "17") (pinfunction "17_(28)_17") (pintype "bidirectional"))
    )
    (net (code "64") (name "unconnected-(Uesp-18_(29)-Pad18)") (class "Default")
      (node (ref "Uesp") (pin "18") (pinfunction "18_(29)_18") (pintype "bidirectional"))
    )
    (net (code "65") (name "unconnected-(Uesp-19_(30)-Pad19)") (class "Default")
      (node (ref "Uesp") (pin "19") (pinfunction "19_(30)_19") (pintype "bidirectional"))
    )
    (net (code "66") (name "unconnected-(Uesp-20_(31)-Pad20)") (class "Default")
      (node (ref "Uesp") (pin "20") (pinfunction "20_(31)_20") (pintype "bidirectional"))
    )
    (net (code "67") (name "unconnected-(Uesp-21_(32)-Pad21)") (class "Default")
      (node (ref "Uesp") (pin "21") (pinfunction "21_(32)_21") (pintype "bidirectional"))
    )
    (net (code "68") (name "unconnected-(Uesp-22_(33)-Pad22)") (class "Default")
      (node (ref "Uesp") (pin "22") (pinfunction "22_(33)_22") (pintype "bidirectional"))
    )
  )
)
